# Boost.net
KiCad netlist of a schematic drawn in Altium Designer
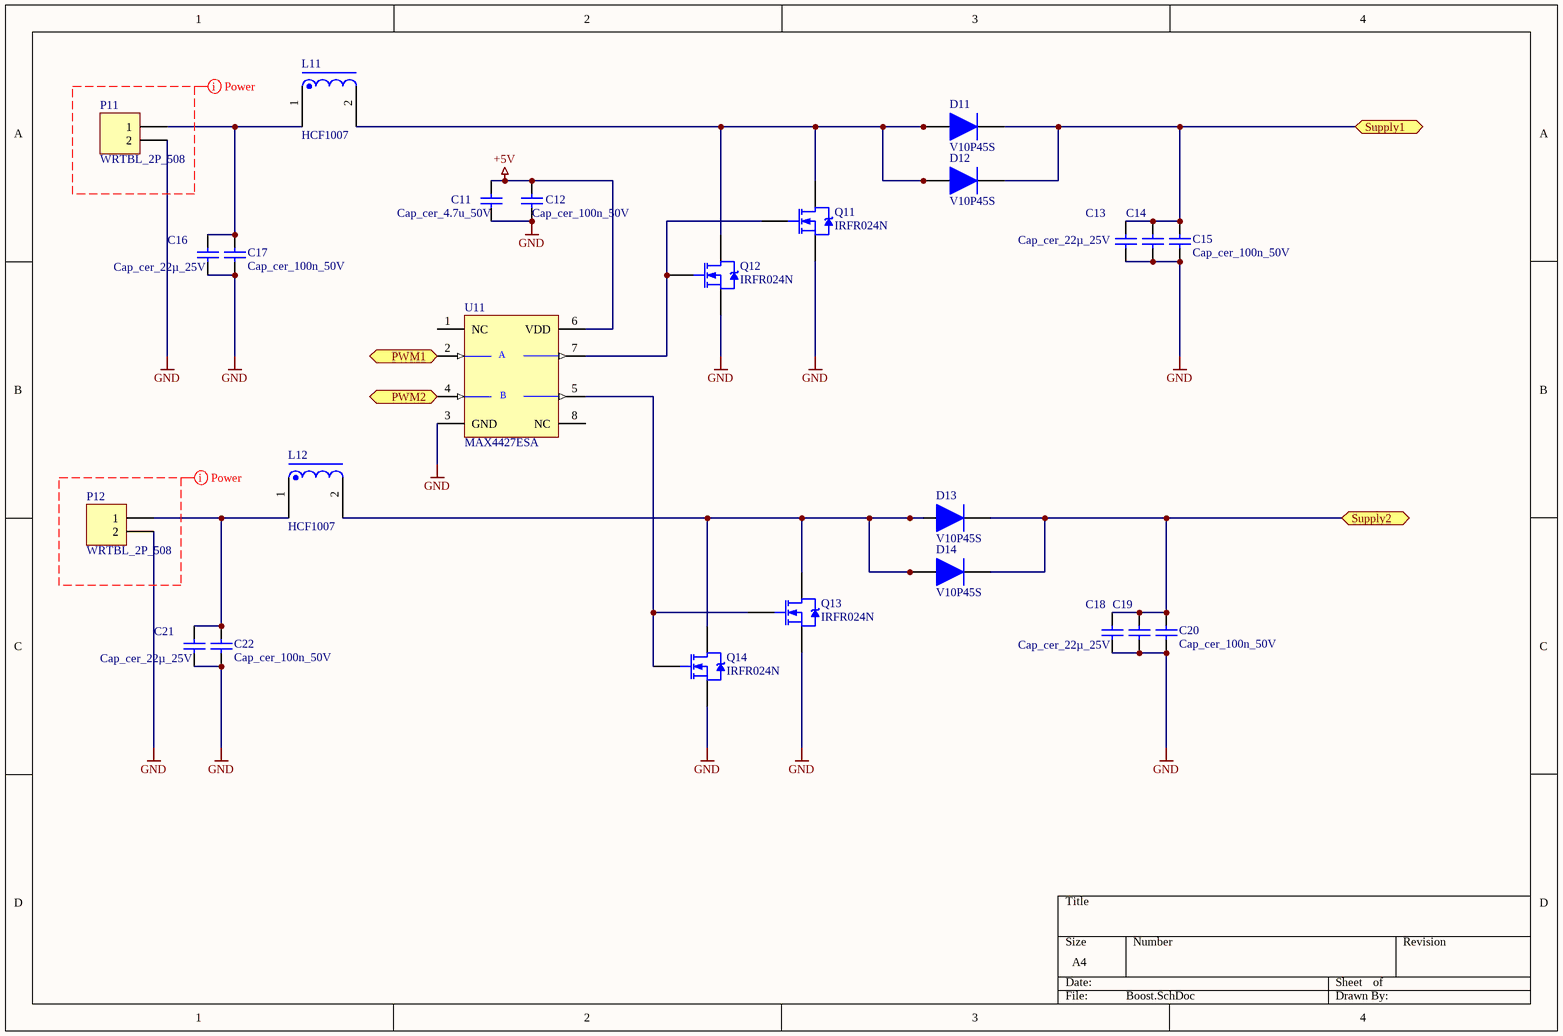
[diagram p0: Boost.SchDoc]

(export (version "E")
  (design (tool "Eeschema 10.0.6"))
  (components
    (comp (ref "C11")
      (value "Cap_cer_4.7u_50V")
      (footprint "_0805")
      (fields (field (name "VOLTAGE") "50V"))
      (libsource (lib "Capacitors$") (part "Cap_124"))
    )
    (comp (ref "C12")
      (value "Cap_cer_100n_50V")
      (footprint "_0805")
      (fields (field (name "VOLTAGE") "50V"))
      (libsource (lib "Capacitors$") (part "Cap_124"))
    )
    (comp (ref "C13")
      (value "~")
      (footprint "_0805")
      (fields (field (name "VOLTAGE") "25V"))
      (libsource (lib "Capacitors$") (part "Cap_124"))
    )
    (comp (ref "C14")
      (value "Cap_cer_22µ_25V")
      (footprint "_0805")
      (fields (field (name "VOLTAGE") "25V"))
      (libsource (lib "Capacitors$") (part "Cap_124"))
    )
    (comp (ref "C15")
      (value "Cap_cer_100n_50V")
      (footprint "_0805")
      (fields (field (name "VOLTAGE") "50V"))
      (libsource (lib "Capacitors$") (part "Cap_124"))
    )
    (comp (ref "C16")
      (value "Cap_cer_22µ_25V")
      (footprint "_0805")
      (fields (field (name "VOLTAGE") "25V"))
      (libsource (lib "Capacitors$") (part "Cap_124"))
    )
    (comp (ref "C17")
      (value "Cap_cer_100n_50V")
      (footprint "_0805")
      (fields (field (name "VOLTAGE") "50V"))
      (libsource (lib "Capacitors$") (part "Cap_124"))
    )
    (comp (ref "C18")
      (value "Cap_cer_22µ_25V")
      (footprint "_0805")
      (fields (field (name "VOLTAGE") "25V"))
      (libsource (lib "Capacitors$") (part "Cap_124"))
    )
    (comp (ref "C19")
      (value "Cap_cer_22µ_25V")
      (footprint "_0805")
      (fields (field (name "VOLTAGE") "25V"))
      (libsource (lib "Capacitors$") (part "Cap_124"))
    )
    (comp (ref "C20")
      (value "Cap_cer_100n_50V")
      (footprint "_0805")
      (fields (field (name "VOLTAGE") "50V"))
      (libsource (lib "Capacitors$") (part "Cap_124"))
    )
    (comp (ref "C21")
      (value "Cap_cer_22µ_25V")
      (footprint "_0805")
      (fields (field (name "VOLTAGE") "25V"))
      (libsource (lib "Capacitors$") (part "Cap_124"))
    )
    (comp (ref "C22")
      (value "Cap_cer_100n_50V")
      (footprint "_0805")
      (fields (field (name "VOLTAGE") "50V"))
      (libsource (lib "Capacitors$") (part "Cap_124"))
    )
    (comp (ref "D11")
      (value "V10P45S")
      (footprint "TO-277A")
      (description "V01P45 Shottky Diode")
      (libsource (lib "Project_Components") (part "V10P45S"))
    )
    (comp (ref "D12")
      (value "V10P45S")
      (footprint "TO-277A")
      (description "V01P45 Shottky Diode")
      (libsource (lib "Project_Components") (part "V10P45S"))
    )
    (comp (ref "D13")
      (value "V10P45S")
      (footprint "TO-277A")
      (description "V01P45 Shottky Diode")
      (libsource (lib "Project_Components") (part "V10P45S"))
    )
    (comp (ref "D14")
      (value "V10P45S")
      (footprint "TO-277A")
      (description "V01P45 Shottky Diode")
      (libsource (lib "Project_Components") (part "V10P45S"))
    )
    (comp (ref "L11")
      (value "HCF1007")
      (footprint "HCF1007")
      (description "HCF1007 Inductor")
      (libsource (lib "Project_Components") (part "HCF1007"))
    )
    (comp (ref "L12")
      (value "HCF1007")
      (footprint "HCF1007")
      (description "HCF1007 Inductor")
      (libsource (lib "Project_Components") (part "HCF1007"))
    )
    (comp (ref "P11")
      (value "WRTBL_2P_508")
      (footprint "WRTBL_2P_508")
      (libsource (lib "Connectors$") (part "Con_7"))
    )
    (comp (ref "P12")
      (value "WRTBL_2P_508")
      (footprint "WRTBL_2P_508")
      (libsource (lib "Connectors$") (part "Con_7"))
    )
    (comp (ref "Q11")
      (value "IRFR024N")
      (footprint "TO-252AA_N")
      (description "HEXFET N-Channel Power MOSFET")
      (fields (field (name "PUBLISHER") "Altium Limited"))
      (libsource (lib "IR Discrete MOSFET - Power") (part "IRFR024N"))
    )
    (comp (ref "Q12")
      (value "IRFR024N")
      (footprint "TO-252AA_N")
      (description "HEXFET N-Channel Power MOSFET")
      (fields (field (name "PUBLISHER") "Altium Limited"))
      (libsource (lib "IR Discrete MOSFET - Power") (part "IRFR024N"))
    )
    (comp (ref "Q13")
      (value "IRFR024N")
      (footprint "TO-252AA_N")
      (description "HEXFET N-Channel Power MOSFET")
      (fields (field (name "PUBLISHER") "Altium Limited"))
      (libsource (lib "IR Discrete MOSFET - Power") (part "IRFR024N"))
    )
    (comp (ref "Q14")
      (value "IRFR024N")
      (footprint "TO-252AA_N")
      (description "HEXFET N-Channel Power MOSFET")
      (fields (field (name "PUBLISHER") "Altium Limited"))
      (libsource (lib "IR Discrete MOSFET - Power") (part "IRFR024N"))
    )
    (comp (ref "U11")
      (value "MAX4427ESA")
      (footprint "NSO8_N")
      (description "Dual High-Speed 1.5A MOSFET Driver")
      (fields (field (name "PUBLISHER") "Altium Limited"))
      (libsource (lib "Maxim Interface MOSFET Driver") (part "MAX4427ESA"))
    )
  )
  (nets
    (net (code "1") (name "+5V") (class "Default")
      (node (ref "C11") (pin "2") (pinfunction "2_2") (pintype "passive"))
      (node (ref "C12") (pin "2") (pinfunction "2_2") (pintype "passive"))
      (node (ref "U11") (pin "6") (pinfunction "VDD_6") (pintype "power_in"))
    )
    (net (code "2") (name "/PWM1") (class "Default")
      (node (ref "U11") (pin "2") (pinfunction "INA_2") (pintype "input"))
    )
    (net (code "3") (name "/PWM2") (class "Default")
      (node (ref "U11") (pin "4") (pinfunction "INB_4") (pintype "input"))
    )
    (net (code "4") (name "/Supply1") (class "Default")
      (node (ref "C13") (pin "2") (pinfunction "2_2") (pintype "passive"))
      (node (ref "C14") (pin "2") (pinfunction "2_2") (pintype "passive"))
      (node (ref "C15") (pin "2") (pinfunction "2_2") (pintype "passive"))
      (node (ref "D11") (pin "K") (pinfunction "K_K") (pintype "passive"))
      (node (ref "D12") (pin "K") (pinfunction "K_K") (pintype "passive"))
    )
    (net (code "5") (name "/Supply2") (class "Default")
      (node (ref "C18") (pin "2") (pinfunction "2_2") (pintype "passive"))
      (node (ref "C19") (pin "2") (pinfunction "2_2") (pintype "passive"))
      (node (ref "C20") (pin "2") (pinfunction "2_2") (pintype "passive"))
      (node (ref "D13") (pin "K") (pinfunction "K_K") (pintype "passive"))
      (node (ref "D14") (pin "K") (pinfunction "K_K") (pintype "passive"))
    )
    (net (code "6") (name "GND") (class "Default")
      (node (ref "C11") (pin "1") (pinfunction "1_1") (pintype "passive"))
      (node (ref "C12") (pin "1") (pinfunction "1_1") (pintype "passive"))
      (node (ref "C13") (pin "1") (pinfunction "1_1") (pintype "passive"))
      (node (ref "C14") (pin "1") (pinfunction "1_1") (pintype "passive"))
      (node (ref "C15") (pin "1") (pinfunction "1_1") (pintype "passive"))
      (node (ref "C16") (pin "1") (pinfunction "1_1") (pintype "passive"))
      (node (ref "C17") (pin "1") (pinfunction "1_1") (pintype "passive"))
      (node (ref "C18") (pin "1") (pinfunction "1_1") (pintype "passive"))
      (node (ref "C19") (pin "1") (pinfunction "1_1") (pintype "passive"))
      (node (ref "C20") (pin "1") (pinfunction "1_1") (pintype "passive"))
      (node (ref "C21") (pin "1") (pinfunction "1_1") (pintype "passive"))
      (node (ref "C22") (pin "1") (pinfunction "1_1") (pintype "passive"))
      (node (ref "P11") (pin "2") (pinfunction "2_2") (pintype "passive"))
      (node (ref "P12") (pin "2") (pinfunction "2_2") (pintype "passive"))
      (node (ref "Q11") (pin "3") (pinfunction "S_3") (pintype "passive"))
      (node (ref "Q12") (pin "3") (pinfunction "S_3") (pintype "passive"))
      (node (ref "Q13") (pin "3") (pinfunction "S_3") (pintype "passive"))
      (node (ref "Q14") (pin "3") (pinfunction "S_3") (pintype "passive"))
      (node (ref "U11") (pin "3") (pinfunction "GND_3") (pintype "power_in"))
    )
    (net (code "7") (name "Net-(C16-Pad2)") (class "Default")
      (node (ref "C16") (pin "2") (pinfunction "2_2") (pintype "passive"))
      (node (ref "C17") (pin "2") (pinfunction "2_2") (pintype "passive"))
      (node (ref "L11") (pin "1") (pinfunction "1_1") (pintype "passive"))
      (node (ref "P11") (pin "1") (pinfunction "1_1") (pintype "passive"))
    )
    (net (code "8") (name "Net-(C21-Pad2)") (class "Default")
      (node (ref "C21") (pin "2") (pinfunction "2_2") (pintype "passive"))
      (node (ref "C22") (pin "2") (pinfunction "2_2") (pintype "passive"))
      (node (ref "L12") (pin "1") (pinfunction "1_1") (pintype "passive"))
      (node (ref "P12") (pin "1") (pinfunction "1_1") (pintype "passive"))
    )
    (net (code "9") (name "Net-(Q11-D)") (class "Default")
      (node (ref "D11") (pin "A") (pinfunction "A_A") (pintype "passive"))
      (node (ref "D12") (pin "A") (pinfunction "A_A") (pintype "passive"))
      (node (ref "L11") (pin "2") (pinfunction "2_2") (pintype "passive"))
      (node (ref "Q11") (pin "4") (pinfunction "D_4") (pintype "passive"))
      (node (ref "Q12") (pin "4") (pinfunction "D_4") (pintype "passive"))
    )
    (net (code "10") (name "Net-(Q11-G)") (class "Default")
      (node (ref "Q11") (pin "1") (pinfunction "G_1") (pintype "passive"))
      (node (ref "Q12") (pin "1") (pinfunction "G_1") (pintype "passive"))
      (node (ref "U11") (pin "7") (pinfunction "OUTA_7") (pintype "output"))
    )
    (net (code "11") (name "Net-(Q13-D)") (class "Default")
      (node (ref "D13") (pin "A") (pinfunction "A_A") (pintype "passive"))
      (node (ref "D14") (pin "A") (pinfunction "A_A") (pintype "passive"))
      (node (ref "L12") (pin "2") (pinfunction "2_2") (pintype "passive"))
      (node (ref "Q13") (pin "4") (pinfunction "D_4") (pintype "passive"))
      (node (ref "Q14") (pin "4") (pinfunction "D_4") (pintype "passive"))
    )
    (net (code "12") (name "Net-(Q13-G)") (class "Default")
      (node (ref "Q13") (pin "1") (pinfunction "G_1") (pintype "passive"))
      (node (ref "Q14") (pin "1") (pinfunction "G_1") (pintype "passive"))
      (node (ref "U11") (pin "5") (pinfunction "OUTB_5") (pintype "output"))
    )
    (net (code "13") (name "unconnected-(U11-NC-Pad1)") (class "Default")
      (node (ref "U11") (pin "1") (pinfunction "NC_1") (pintype "passive"))
    )
    (net (code "14") (name "unconnected-(U11-NC-Pad8)") (class "Default")
      (node (ref "U11") (pin "8") (pinfunction "NC_8") (pintype "passive"))
    )
  )
)
